# riffle-CTL-0_3-cap.net
KiCad netlist of a schematic drawn in EAGLE
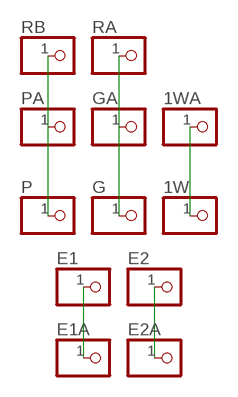
[diagram p0: schematic, sheet 1]

(export (version "E")
  (design (tool "Eeschema 10.0.6"))
  (components
    (comp (ref "1W")
      (value "PINHD-1X1")
      (footprint "eagle-import:1X01")
      (libsource (lib "eagle-import") (part "PINHD-1X1"))
    )
    (comp (ref "1WA")
      (value "PINHD-1X1")
      (footprint "eagle-import:1X01")
      (libsource (lib "eagle-import") (part "PINHD-1X1"))
    )
    (comp (ref "E1")
      (value "PINHD-1X1")
      (footprint "eagle-import:1X01")
      (libsource (lib "eagle-import") (part "PINHD-1X1"))
    )
    (comp (ref "E1A")
      (value "PINHD-1X1")
      (footprint "eagle-import:1X01")
      (libsource (lib "eagle-import") (part "PINHD-1X1"))
    )
    (comp (ref "E2")
      (value "PINHD-1X1")
      (footprint "eagle-import:1X01")
      (libsource (lib "eagle-import") (part "PINHD-1X1"))
    )
    (comp (ref "E2A")
      (value "PINHD-1X1")
      (footprint "eagle-import:1X01")
      (libsource (lib "eagle-import") (part "PINHD-1X1"))
    )
    (comp (ref "G")
      (value "PINHD-1X1")
      (footprint "eagle-import:1X01")
      (libsource (lib "eagle-import") (part "PINHD-1X1"))
    )
    (comp (ref "GA")
      (value "PINHD-1X1")
      (footprint "eagle-import:1X01")
      (libsource (lib "eagle-import") (part "PINHD-1X1"))
    )
    (comp (ref "P")
      (value "PINHD-1X1")
      (footprint "eagle-import:1X01")
      (libsource (lib "eagle-import") (part "PINHD-1X1"))
    )
    (comp (ref "PA")
      (value "PINHD-1X1")
      (footprint "eagle-import:1X01")
      (libsource (lib "eagle-import") (part "PINHD-1X1"))
    )
    (comp (ref "RA")
      (value "PINHD-1X1")
      (footprint "eagle-import:1X01")
      (libsource (lib "eagle-import") (part "PINHD-1X1"))
    )
    (comp (ref "RB")
      (value "PINHD-1X1")
      (footprint "eagle-import:1X01")
      (libsource (lib "eagle-import") (part "PINHD-1X1"))
    )
  )
  (nets
    (net (code "1") (name "Net-(1W-Pad1)") (class "Default")
      (node (ref "1W") (pin "1") (pinfunction "1_1") (pintype "passive"))
      (node (ref "1WA") (pin "1") (pinfunction "1_1") (pintype "passive"))
    )
    (net (code "2") (name "Net-(E1-Pad1)") (class "Default")
      (node (ref "E1") (pin "1") (pinfunction "1_1") (pintype "passive"))
      (node (ref "E1A") (pin "1") (pinfunction "1_1") (pintype "passive"))
    )
    (net (code "3") (name "Net-(E2-Pad1)") (class "Default")
      (node (ref "E2") (pin "1") (pinfunction "1_1") (pintype "passive"))
      (node (ref "E2A") (pin "1") (pinfunction "1_1") (pintype "passive"))
    )
    (net (code "4") (name "Net-(G-Pad1)") (class "Default")
      (node (ref "G") (pin "1") (pinfunction "1_1") (pintype "passive"))
      (node (ref "GA") (pin "1") (pinfunction "1_1") (pintype "passive"))
      (node (ref "RA") (pin "1") (pinfunction "1_1") (pintype "passive"))
    )
    (net (code "5") (name "Net-(P-Pad1)") (class "Default")
      (node (ref "P") (pin "1") (pinfunction "1_1") (pintype "passive"))
      (node (ref "PA") (pin "1") (pinfunction "1_1") (pintype "passive"))
      (node (ref "RB") (pin "1") (pinfunction "1_1") (pintype "passive"))
    )
  )
)
